# ring.net
KiCad netlist of a schematic drawn in EAGLE
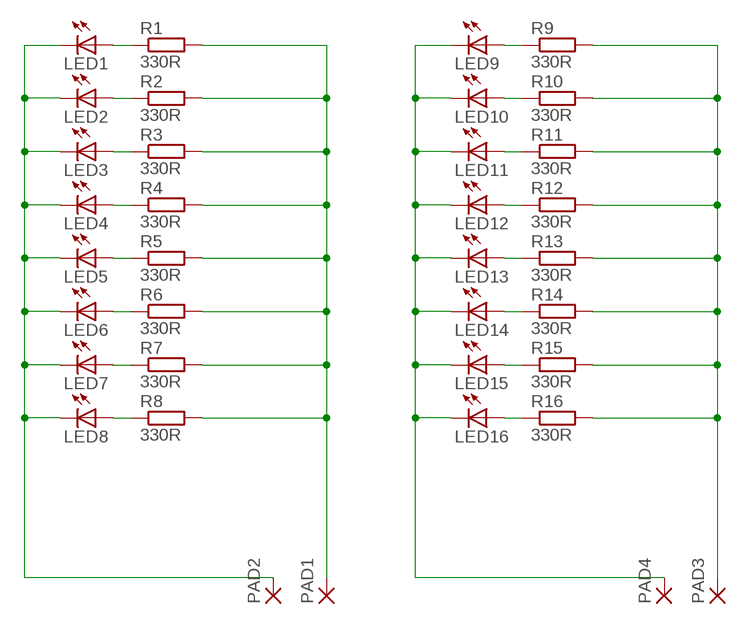
[diagram p0: schematic, sheet 1]

(export (version "E")
  (design (tool "Eeschema 10.0.6"))
  (components
    (comp (ref "LED1")
      (value "LEDKA-3528ASYC")
      (footprint "eagle-import:KA-3528ASYC")
      (libsource (lib "eagle-import") (part "LEDKA-3528ASYC"))
    )
    (comp (ref "LED2")
      (value "LEDKA-3528ASYC")
      (footprint "eagle-import:KA-3528ASYC")
      (libsource (lib "eagle-import") (part "LEDKA-3528ASYC"))
    )
    (comp (ref "LED3")
      (value "LEDKA-3528ASYC")
      (footprint "eagle-import:KA-3528ASYC")
      (libsource (lib "eagle-import") (part "LEDKA-3528ASYC"))
    )
    (comp (ref "LED4")
      (value "LEDKA-3528ASYC")
      (footprint "eagle-import:KA-3528ASYC")
      (libsource (lib "eagle-import") (part "LEDKA-3528ASYC"))
    )
    (comp (ref "LED5")
      (value "LEDKA-3528ASYC")
      (footprint "eagle-import:KA-3528ASYC")
      (libsource (lib "eagle-import") (part "LEDKA-3528ASYC"))
    )
    (comp (ref "LED6")
      (value "LEDKA-3528ASYC")
      (footprint "eagle-import:KA-3528ASYC")
      (libsource (lib "eagle-import") (part "LEDKA-3528ASYC"))
    )
    (comp (ref "LED7")
      (value "LEDKA-3528ASYC")
      (footprint "eagle-import:KA-3528ASYC")
      (libsource (lib "eagle-import") (part "LEDKA-3528ASYC"))
    )
    (comp (ref "LED8")
      (value "LEDKA-3528ASYC")
      (footprint "eagle-import:KA-3528ASYC")
      (libsource (lib "eagle-import") (part "LEDKA-3528ASYC"))
    )
    (comp (ref "LED9")
      (value "LEDKA-3528ASYC")
      (footprint "eagle-import:KA-3528ASYC")
      (libsource (lib "eagle-import") (part "LEDKA-3528ASYC"))
    )
    (comp (ref "LED10")
      (value "LEDKA-3528ASYC")
      (footprint "eagle-import:KA-3528ASYC")
      (libsource (lib "eagle-import") (part "LEDKA-3528ASYC"))
    )
    (comp (ref "LED11")
      (value "LEDKA-3528ASYC")
      (footprint "eagle-import:KA-3528ASYC")
      (libsource (lib "eagle-import") (part "LEDKA-3528ASYC"))
    )
    (comp (ref "LED12")
      (value "LEDKA-3528ASYC")
      (footprint "eagle-import:KA-3528ASYC")
      (libsource (lib "eagle-import") (part "LEDKA-3528ASYC"))
    )
    (comp (ref "LED13")
      (value "LEDKA-3528ASYC")
      (footprint "eagle-import:KA-3528ASYC")
      (libsource (lib "eagle-import") (part "LEDKA-3528ASYC"))
    )
    (comp (ref "LED14")
      (value "LEDKA-3528ASYC")
      (footprint "eagle-import:KA-3528ASYC")
      (libsource (lib "eagle-import") (part "LEDKA-3528ASYC"))
    )
    (comp (ref "LED15")
      (value "LEDKA-3528ASYC")
      (footprint "eagle-import:KA-3528ASYC")
      (libsource (lib "eagle-import") (part "LEDKA-3528ASYC"))
    )
    (comp (ref "LED16")
      (value "LEDKA-3528ASYC")
      (footprint "eagle-import:KA-3528ASYC")
      (libsource (lib "eagle-import") (part "LEDKA-3528ASYC"))
    )
    (comp (ref "PAD1")
      (value "SMD2")
      (footprint "eagle-import:SMD1,27-2,54")
      (libsource (lib "eagle-import") (part "SMD2"))
    )
    (comp (ref "PAD2")
      (value "SMD2")
      (footprint "eagle-import:SMD1,27-2,54")
      (libsource (lib "eagle-import") (part "SMD2"))
    )
    (comp (ref "PAD3")
      (value "SMD2")
      (footprint "eagle-import:SMD1,27-2,54")
      (libsource (lib "eagle-import") (part "SMD2"))
    )
    (comp (ref "PAD4")
      (value "SMD2")
      (footprint "eagle-import:SMD1,27-2,54")
      (libsource (lib "eagle-import") (part "SMD2"))
    )
    (comp (ref "R1")
      (value "330R")
      (footprint "eagle-import:R0805W")
      (libsource (lib "eagle-import") (part "R-EU_R0805W"))
    )
    (comp (ref "R2")
      (value "330R")
      (footprint "eagle-import:R0805W")
      (libsource (lib "eagle-import") (part "R-EU_R0805W"))
    )
    (comp (ref "R3")
      (value "330R")
      (footprint "eagle-import:R0805W")
      (libsource (lib "eagle-import") (part "R-EU_R0805W"))
    )
    (comp (ref "R4")
      (value "330R")
      (footprint "eagle-import:R0805W")
      (libsource (lib "eagle-import") (part "R-EU_R0805W"))
    )
    (comp (ref "R5")
      (value "330R")
      (footprint "eagle-import:R0805W")
      (libsource (lib "eagle-import") (part "R-EU_R0805W"))
    )
    (comp (ref "R6")
      (value "330R")
      (footprint "eagle-import:R0805W")
      (libsource (lib "eagle-import") (part "R-EU_R0805W"))
    )
    (comp (ref "R7")
      (value "330R")
      (footprint "eagle-import:R0805W")
      (libsource (lib "eagle-import") (part "R-EU_R0805W"))
    )
    (comp (ref "R8")
      (value "330R")
      (footprint "eagle-import:R0805W")
      (libsource (lib "eagle-import") (part "R-EU_R0805W"))
    )
    (comp (ref "R9")
      (value "330R")
      (footprint "eagle-import:R0805W")
      (libsource (lib "eagle-import") (part "R-EU_R0805W"))
    )
    (comp (ref "R10")
      (value "330R")
      (footprint "eagle-import:R0805W")
      (libsource (lib "eagle-import") (part "R-EU_R0805W"))
    )
    (comp (ref "R11")
      (value "330R")
      (footprint "eagle-import:R0805W")
      (libsource (lib "eagle-import") (part "R-EU_R0805W"))
    )
    (comp (ref "R12")
      (value "330R")
      (footprint "eagle-import:R0805W")
      (libsource (lib "eagle-import") (part "R-EU_R0805W"))
    )
    (comp (ref "R13")
      (value "330R")
      (footprint "eagle-import:R0805W")
      (libsource (lib "eagle-import") (part "R-EU_R0805W"))
    )
    (comp (ref "R14")
      (value "330R")
      (footprint "eagle-import:R0805W")
      (libsource (lib "eagle-import") (part "R-EU_R0805W"))
    )
    (comp (ref "R15")
      (value "330R")
      (footprint "eagle-import:R0805W")
      (libsource (lib "eagle-import") (part "R-EU_R0805W"))
    )
    (comp (ref "R16")
      (value "330R")
      (footprint "eagle-import:R0805W")
      (libsource (lib "eagle-import") (part "R-EU_R0805W"))
    )
  )
  (nets
    (net (code "1") (name "Net-(LED1-PadA)") (class "Default")
      (node (ref "LED1") (pin "A") (pinfunction "A_A") (pintype "passive"))
      (node (ref "R1") (pin "1") (pinfunction "1_1") (pintype "passive"))
    )
    (net (code "2") (name "Net-(LED2-PadA)") (class "Default")
      (node (ref "LED2") (pin "A") (pinfunction "A_A") (pintype "passive"))
      (node (ref "R2") (pin "1") (pinfunction "1_1") (pintype "passive"))
    )
    (net (code "3") (name "Net-(LED3-PadA)") (class "Default")
      (node (ref "LED3") (pin "A") (pinfunction "A_A") (pintype "passive"))
      (node (ref "R3") (pin "1") (pinfunction "1_1") (pintype "passive"))
    )
    (net (code "4") (name "Net-(LED4-PadA)") (class "Default")
      (node (ref "LED4") (pin "A") (pinfunction "A_A") (pintype "passive"))
      (node (ref "R4") (pin "1") (pinfunction "1_1") (pintype "passive"))
    )
    (net (code "5") (name "Net-(LED5-PadA)") (class "Default")
      (node (ref "LED5") (pin "A") (pinfunction "A_A") (pintype "passive"))
      (node (ref "R5") (pin "1") (pinfunction "1_1") (pintype "passive"))
    )
    (net (code "6") (name "Net-(LED6-PadA)") (class "Default")
      (node (ref "LED6") (pin "A") (pinfunction "A_A") (pintype "passive"))
      (node (ref "R6") (pin "1") (pinfunction "1_1") (pintype "passive"))
    )
    (net (code "7") (name "Net-(LED7-PadA)") (class "Default")
      (node (ref "LED7") (pin "A") (pinfunction "A_A") (pintype "passive"))
      (node (ref "R7") (pin "1") (pinfunction "1_1") (pintype "passive"))
    )
    (net (code "8") (name "Net-(LED8-PadA)") (class "Default")
      (node (ref "LED8") (pin "A") (pinfunction "A_A") (pintype "passive"))
      (node (ref "R8") (pin "1") (pinfunction "1_1") (pintype "passive"))
    )
    (net (code "9") (name "Net-(LED9-PadA)") (class "Default")
      (node (ref "LED9") (pin "A") (pinfunction "A_A") (pintype "passive"))
      (node (ref "R9") (pin "1") (pinfunction "1_1") (pintype "passive"))
    )
    (net (code "10") (name "Net-(LED10-PadA)") (class "Default")
      (node (ref "LED10") (pin "A") (pinfunction "A_A") (pintype "passive"))
      (node (ref "R10") (pin "1") (pinfunction "1_1") (pintype "passive"))
    )
    (net (code "11") (name "Net-(LED11-PadA)") (class "Default")
      (node (ref "LED11") (pin "A") (pinfunction "A_A") (pintype "passive"))
      (node (ref "R11") (pin "1") (pinfunction "1_1") (pintype "passive"))
    )
    (net (code "12") (name "Net-(LED12-PadA)") (class "Default")
      (node (ref "LED12") (pin "A") (pinfunction "A_A") (pintype "passive"))
      (node (ref "R12") (pin "1") (pinfunction "1_1") (pintype "passive"))
    )
    (net (code "13") (name "Net-(LED13-PadA)") (class "Default")
      (node (ref "LED13") (pin "A") (pinfunction "A_A") (pintype "passive"))
      (node (ref "R13") (pin "1") (pinfunction "1_1") (pintype "passive"))
    )
    (net (code "14") (name "Net-(LED14-PadA)") (class "Default")
      (node (ref "LED14") (pin "A") (pinfunction "A_A") (pintype "passive"))
      (node (ref "R14") (pin "1") (pinfunction "1_1") (pintype "passive"))
    )
    (net (code "15") (name "Net-(LED15-PadA)") (class "Default")
      (node (ref "LED15") (pin "A") (pinfunction "A_A") (pintype "passive"))
      (node (ref "R15") (pin "1") (pinfunction "1_1") (pintype "passive"))
    )
    (net (code "16") (name "Net-(LED16-PadA)") (class "Default")
      (node (ref "LED16") (pin "A") (pinfunction "A_A") (pintype "passive"))
      (node (ref "R16") (pin "1") (pinfunction "1_1") (pintype "passive"))
    )
    (net (code "17") (name "Net-(PAD1-P)") (class "Default")
      (node (ref "PAD1") (pin "1") (pinfunction "P_1") (pintype "passive"))
      (node (ref "R1") (pin "2") (pinfunction "2_2") (pintype "passive"))
      (node (ref "R2") (pin "2") (pinfunction "2_2") (pintype "passive"))
      (node (ref "R3") (pin "2") (pinfunction "2_2") (pintype "passive"))
      (node (ref "R4") (pin "2") (pinfunction "2_2") (pintype "passive"))
      (node (ref "R5") (pin "2") (pinfunction "2_2") (pintype "passive"))
      (node (ref "R6") (pin "2") (pinfunction "2_2") (pintype "passive"))
      (node (ref "R7") (pin "2") (pinfunction "2_2") (pintype "passive"))
      (node (ref "R8") (pin "2") (pinfunction "2_2") (pintype "passive"))
    )
    (net (code "18") (name "Net-(PAD2-P)") (class "Default")
      (node (ref "LED1") (pin "C") (pinfunction "C_C") (pintype "passive"))
      (node (ref "LED2") (pin "C") (pinfunction "C_C") (pintype "passive"))
      (node (ref "LED3") (pin "C") (pinfunction "C_C") (pintype "passive"))
      (node (ref "LED4") (pin "C") (pinfunction "C_C") (pintype "passive"))
      (node (ref "LED5") (pin "C") (pinfunction "C_C") (pintype "passive"))
      (node (ref "LED6") (pin "C") (pinfunction "C_C") (pintype "passive"))
      (node (ref "LED7") (pin "C") (pinfunction "C_C") (pintype "passive"))
      (node (ref "LED8") (pin "C") (pinfunction "C_C") (pintype "passive"))
      (node (ref "PAD2") (pin "1") (pinfunction "P_1") (pintype "passive"))
    )
    (net (code "19") (name "Net-(PAD3-P)") (class "Default")
      (node (ref "PAD3") (pin "1") (pinfunction "P_1") (pintype "passive"))
      (node (ref "R10") (pin "2") (pinfunction "2_2") (pintype "passive"))
      (node (ref "R11") (pin "2") (pinfunction "2_2") (pintype "passive"))
      (node (ref "R12") (pin "2") (pinfunction "2_2") (pintype "passive"))
      (node (ref "R13") (pin "2") (pinfunction "2_2") (pintype "passive"))
      (node (ref "R14") (pin "2") (pinfunction "2_2") (pintype "passive"))
      (node (ref "R15") (pin "2") (pinfunction "2_2") (pintype "passive"))
      (node (ref "R16") (pin "2") (pinfunction "2_2") (pintype "passive"))
      (node (ref "R9") (pin "2") (pinfunction "2_2") (pintype "passive"))
    )
    (net (code "20") (name "Net-(PAD4-P)") (class "Default")
      (node (ref "LED10") (pin "C") (pinfunction "C_C") (pintype "passive"))
      (node (ref "LED11") (pin "C") (pinfunction "C_C") (pintype "passive"))
      (node (ref "LED12") (pin "C") (pinfunction "C_C") (pintype "passive"))
      (node (ref "LED13") (pin "C") (pinfunction "C_C") (pintype "passive"))
      (node (ref "LED14") (pin "C") (pinfunction "C_C") (pintype "passive"))
      (node (ref "LED15") (pin "C") (pinfunction "C_C") (pintype "passive"))
      (node (ref "LED16") (pin "C") (pinfunction "C_C") (pintype "passive"))
      (node (ref "LED9") (pin "C") (pinfunction "C_C") (pintype "passive"))
      (node (ref "PAD4") (pin "1") (pinfunction "P_1") (pintype "passive"))
    )
  )
)
